# Sensors.net
KiCad netlist of a schematic drawn in Altium Designer
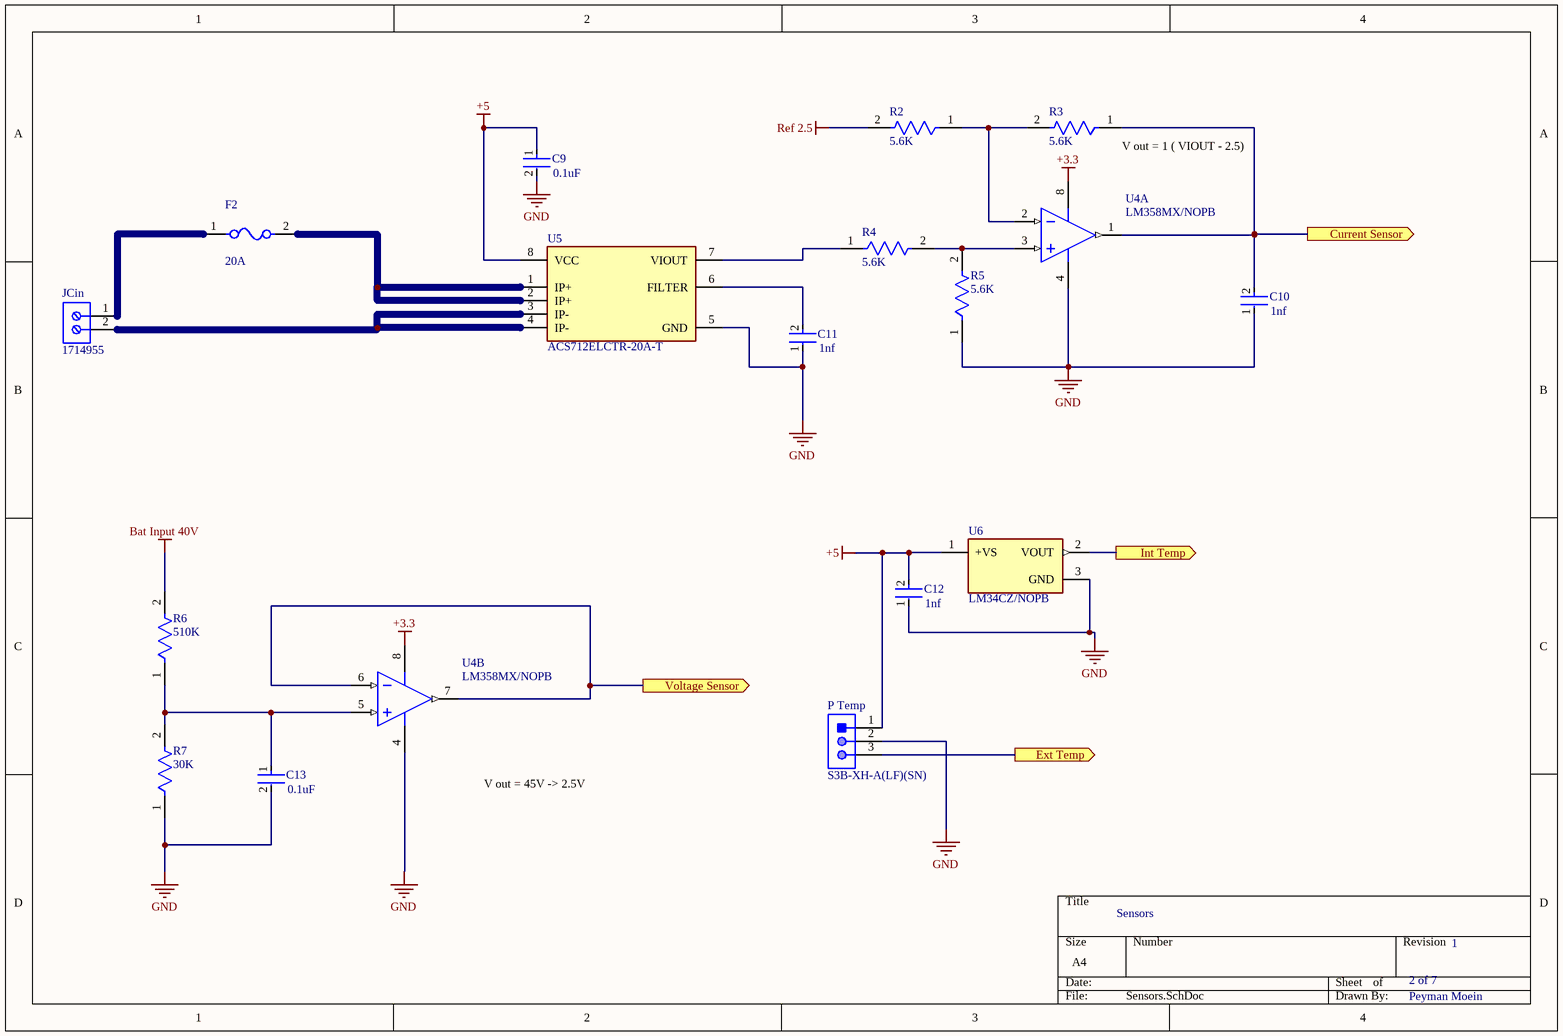
[diagram p0: Sensors.SchDoc]

(export (version "E")
  (design (tool "Eeschema 10.0.6"))
  (components
    (comp (ref "C9")
      (value "0.1uF")
      (footprint "FP-C0805C-DN-MFG")
      (description "C49678")
      (fields (field (name "TOLERANCE") "0.1") (field (name "MANUFACTURER PART NUMBER") "CC0805KRX7R9BB104"))
      (libsource (lib "Altium Content Vault") (part "11868f565c42a9108669ba33697ecf6"))
    )
    (comp (ref "C10")
      (value "1nf")
      (footprint "CAPC2013X70X45NL10T25")
      (description "C303890")
      (fields (field (name "TOLERANCE") "0.1") (field (name "MANUFACTURER PART NUMBER") "CC0805KRX7R9BB104"))
      (libsource (lib "") (part "11868f565c42a9108669ba33697ecf6_1"))
    )
    (comp (ref "C11")
      (value "1nf")
      (footprint "CAPC2013X70X45NL10T25")
      (description "C303890")
      (fields (field (name "TOLERANCE") "0.1") (field (name "MANUFACTURER PART NUMBER") "CC0805KRX7R9BB104"))
      (libsource (lib "") (part "11868f565c42a9108669ba33697ecf6_1"))
    )
    (comp (ref "C12")
      (value "1nf")
      (footprint "CAPC2013X70X45NL10T25")
      (description "C303890")
      (fields (field (name "TOLERANCE") "0.1") (field (name "MANUFACTURER PART NUMBER") "CC0805KRX7R9BB104"))
      (libsource (lib "") (part "11868f565c42a9108669ba33697ecf6_1"))
    )
    (comp (ref "C13")
      (value "0.1uF")
      (footprint "FP-C0805C-DN-MFG")
      (description "C49678")
      (fields (field (name "TOLERANCE") "0.1") (field (name "MANUFACTURER PART NUMBER") "CC0805KRX7R9BB104"))
      (libsource (lib "Altium Content Vault") (part "11868f565c42a9108669ba33697ecf6"))
    )
    (comp (ref "F2")
      (value "20A")
      (footprint "FP-0456-MFG")
      (description "C99552")
      (fields
        (field (name "MANUFACTURER") "Littelfuse Inc")
        (field (name "OCTOPART") "https://octopart.com/0456020.er-littelfuse-7502596")
      )
      (libsource (lib "Altium Content Vault") (part "5bcf9b9f640e542cf0359d10258e979"))
    )
    (comp (ref "JCin")
      (value "1714955")
      (footprint "PHOE-1714955_V")
      (description "PC Terminal Block, Pitch 6.35 mm, 1 x 2 Position, Height 21.5 mm, Tail Lenght 5.1 mm, RoHS, Bulk")
      (fields (field (name "MANUFACTURER") "Phoenix Contact"))
      (libsource (lib "Altium Content Vault") (part "CN-1P-F-TB2"))
    )
    (comp (ref "P Temp")
      (value "S3B-XH-A(LF)(SN)")
      (footprint "JST-S3B-XH-A(LF)(SN)_V")
      (description "C157928")
      (libsource (lib "Altium Content Vault") (part "CN-1P-M-R3"))
    )
    (comp (ref "R2")
      (value "5.6K")
      (footprint "FP-CRCW0805-e3-MFG")
      (description "C4382")
      (fields (field (name "TOLERANCE") "1%"))
      (libsource (lib "Altium Content Vault") (part "1029c3af85768c4190bb7ad29bc67b5"))
    )
    (comp (ref "R3")
      (value "5.6K")
      (footprint "FP-CRCW0805-e3-MFG")
      (description "C4382")
      (fields (field (name "TOLERANCE") "1%"))
      (libsource (lib "Altium Content Vault") (part "1029c3af85768c4190bb7ad29bc67b5"))
    )
    (comp (ref "R4")
      (value "5.6K")
      (footprint "FP-CRCW0805-e3-MFG")
      (description "C4382")
      (fields (field (name "TOLERANCE") "1%"))
      (libsource (lib "Altium Content Vault") (part "1029c3af85768c4190bb7ad29bc67b5"))
    )
    (comp (ref "R5")
      (value "5.6K")
      (footprint "FP-CRCW0805-e3-MFG")
      (description "C4382")
      (fields (field (name "TOLERANCE") "1%"))
      (libsource (lib "Altium Content Vault") (part "1029c3af85768c4190bb7ad29bc67b5"))
    )
    (comp (ref "R6")
      (value "510K")
      (footprint "FP-CRCW0805-e3-MFG")
      (description "C17724")
      (fields (field (name "TOLERANCE") "1%"))
      (libsource (lib "Altium Content Vault") (part "1029c3af85768c4190bb7ad29bc67b5"))
    )
    (comp (ref "R7")
      (value "30K")
      (footprint "FP-CRCW0805-e3-MFG")
      (description "C422839")
      (fields (field (name "TOLERANCE") "1%"))
      (libsource (lib "Altium Content Vault") (part "1029c3af85768c4190bb7ad29bc67b5"))
    )
    (comp (ref "U4")
      (value "LM358MX/NOPB")
      (footprint "D0008A_L")
      (description "C16416")
      (fields (field (name "MANUFACTURER") "Texas Instruments"))
      (libsource (lib "Altium Content Vault") (part "TI-LM358M-8"))
    )
    (comp (ref "U5")
      (value "ACS712ELCTR-20A-T")
      (footprint "FP-LC-8-IPC_C")
      (description "C10681")
      (libsource (lib "Altium Content Vault") (part "c67a3b215a6bf96dc401a72103bae39"))
    )
    (comp (ref "U6")
      (value "LM34CZ/NOPB")
      (footprint "FP-LP0003A-MFG")
      (description "SENSOR ANALOG -40F-230F TO92-3")
      (fields
        (field (name "OCTOPART") "https://octopart.com/lm34cz%2Fnopb-texas+instruments-24813949")
        (field (name "MANUFACTURER") "Texas Instruments")
      )
      (libsource (lib "Altium Content Vault") (part "68e57baa88b61129767e98d35fa11e3"))
    )
  )
  (nets
    (net (code "1") (name "+3.3") (class "Default")
      (node (ref "U4") (pin "8") (pinfunction "V+_8") (pintype "power_in"))
    )
    (net (code "2") (name "+5") (class "Default")
      (node (ref "C12") (pin "2") (pinfunction "2_2") (pintype "passive"))
      (node (ref "C9") (pin "1") (pinfunction "1_1") (pintype "passive"))
      (node (ref "P Temp") (pin "1") (pinfunction "1_1") (pintype "passive"))
      (node (ref "U5") (pin "8") (pinfunction "VCC_8") (pintype "power_in"))
      (node (ref "U6") (pin "1") (pinfunction "+VS_1") (pintype "power_in"))
    )
    (net (code "3") (name "/Current Sensor") (class "Default")
      (node (ref "C10") (pin "2") (pinfunction "2_2") (pintype "passive"))
      (node (ref "R3") (pin "1") (pinfunction "1_1") (pintype "passive"))
      (node (ref "U4") (pin "1") (pinfunction "OUTA_1") (pintype "output"))
    )
    (net (code "4") (name "/Ext Temp") (class "Default")
      (node (ref "P Temp") (pin "3") (pinfunction "3_3") (pintype "passive"))
    )
    (net (code "5") (name "/Int Temp") (class "Default")
      (node (ref "U6") (pin "2") (pinfunction "VOUT_2") (pintype "output"))
    )
    (net (code "6") (name "/Voltage Sensor") (class "Default")
      (node (ref "U4") (pin "6") (pinfunction "-INB_6") (pintype "input"))
      (node (ref "U4") (pin "7") (pinfunction "OUTB_7") (pintype "output"))
    )
    (net (code "7") (name "Bat Input 40V") (class "Default")
      (node (ref "R6") (pin "2") (pinfunction "2_2") (pintype "passive"))
    )
    (net (code "8") (name "GND") (class "Default")
      (node (ref "C10") (pin "1") (pinfunction "1_1") (pintype "passive"))
      (node (ref "C11") (pin "1") (pinfunction "1_1") (pintype "passive"))
      (node (ref "C12") (pin "1") (pinfunction "1_1") (pintype "passive"))
      (node (ref "C13") (pin "2") (pinfunction "2_2") (pintype "passive"))
      (node (ref "C9") (pin "2") (pinfunction "2_2") (pintype "passive"))
      (node (ref "P Temp") (pin "2") (pinfunction "2_2") (pintype "passive"))
      (node (ref "R5") (pin "1") (pinfunction "1_1") (pintype "passive"))
      (node (ref "R7") (pin "1") (pinfunction "1_1") (pintype "passive"))
      (node (ref "U4") (pin "4") (pinfunction "GND/V-_4") (pintype "power_in"))
      (node (ref "U5") (pin "5") (pinfunction "GND_5") (pintype "power_in"))
      (node (ref "U6") (pin "3") (pinfunction "GND_3") (pintype "power_in"))
    )
    (net (code "9") (name "Net-(F2-Pad1)") (class "Default")
      (node (ref "F2") (pin "1") (pinfunction "1_1") (pintype "passive"))
      (node (ref "JCin") (pin "1") (pinfunction "1_1") (pintype "passive"))
    )
    (net (code "10") (name "Net-(F2-Pad2)") (class "Default")
      (node (ref "F2") (pin "2") (pinfunction "2_2") (pintype "passive"))
      (node (ref "U5") (pin "1") (pinfunction "IP+_1") (pintype "passive"))
      (node (ref "U5") (pin "2") (pinfunction "IP+_2") (pintype "passive"))
    )
    (net (code "11") (name "Net-(JCin-Pad2)") (class "Default")
      (node (ref "JCin") (pin "2") (pinfunction "2_2") (pintype "passive"))
      (node (ref "U5") (pin "3") (pinfunction "IP-_3") (pintype "passive"))
      (node (ref "U5") (pin "4") (pinfunction "IP-_4") (pintype "passive"))
    )
    (net (code "12") (name "Net-(U4A-+INA)") (class "Default")
      (node (ref "R4") (pin "2") (pinfunction "2_2") (pintype "passive"))
      (node (ref "R5") (pin "2") (pinfunction "2_2") (pintype "passive"))
      (node (ref "U4") (pin "3") (pinfunction "+INA_3") (pintype "input"))
    )
    (net (code "13") (name "Net-(U4A--INA)") (class "Default")
      (node (ref "R2") (pin "1") (pinfunction "1_1") (pintype "passive"))
      (node (ref "R3") (pin "2") (pinfunction "2_2") (pintype "passive"))
      (node (ref "U4") (pin "2") (pinfunction "-INA_2") (pintype "input"))
    )
    (net (code "14") (name "Net-(U4B-+INB)") (class "Default")
      (node (ref "C13") (pin "1") (pinfunction "1_1") (pintype "passive"))
      (node (ref "R6") (pin "1") (pinfunction "1_1") (pintype "passive"))
      (node (ref "R7") (pin "2") (pinfunction "2_2") (pintype "passive"))
      (node (ref "U4") (pin "5") (pinfunction "+INB_5") (pintype "input"))
    )
    (net (code "15") (name "Net-(U5-FILTER)") (class "Default")
      (node (ref "C11") (pin "2") (pinfunction "2_2") (pintype "passive"))
      (node (ref "U5") (pin "6") (pinfunction "FILTER_6") (pintype "passive"))
    )
    (net (code "16") (name "Net-(U5-VIOUT)") (class "Default")
      (node (ref "R4") (pin "1") (pinfunction "1_1") (pintype "passive"))
      (node (ref "U5") (pin "7") (pinfunction "VIOUT_7") (pintype "passive"))
    )
    (net (code "17") (name "Ref 2.5") (class "Default")
      (node (ref "R2") (pin "2") (pinfunction "2_2") (pintype "passive"))
    )
  )
)
